# Modulator.net
KiCad netlist of a schematic drawn in Altium Designer
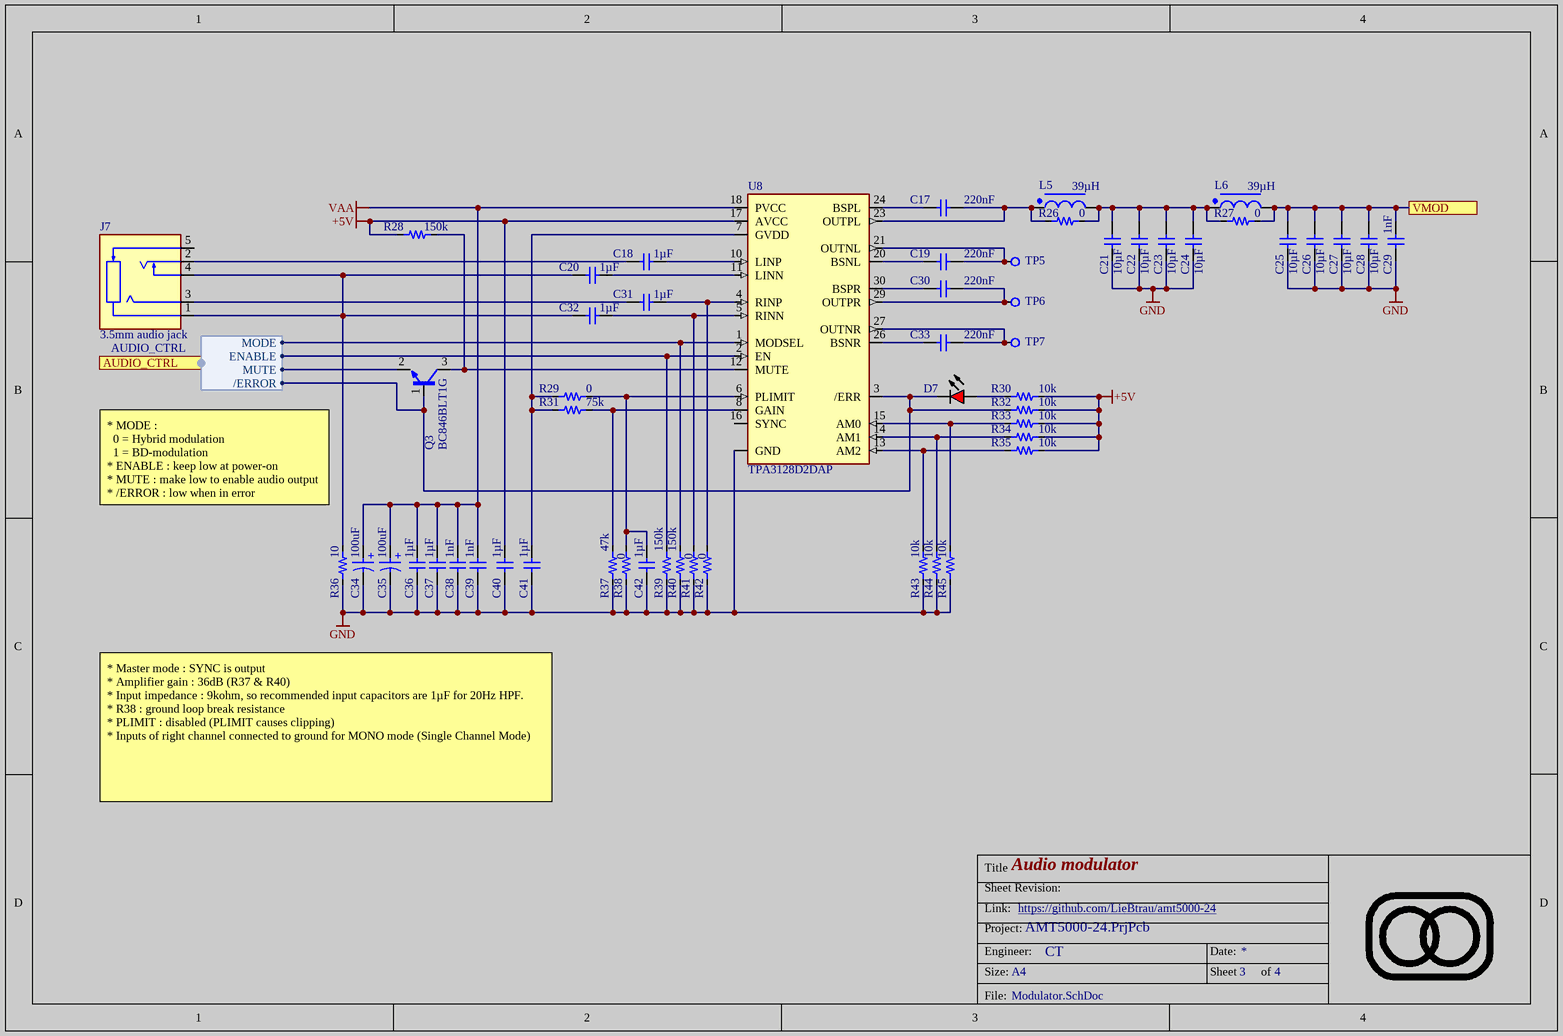
[diagram p0: Modulator.SchDoc]

(export (version "E")
  (design (tool "Eeschema 10.0.6"))
  (components
    (comp (ref "C17")
      (value "220nF")
      (footprint "0805-C-N")
      (description "WCAP-CSGP Multilayer Ceramic Chip Capacitor, General Purpose, size 0805, X7R, 220nF, 50VDC")
      (fields (field (name "JLCPCB PART #") "C5378") (field (name "TOLERANCE") "10%"))
      (libsource (lib "7c7 Engineering") (part "CAP-NP-2"))
    )
    (comp (ref "C18")
      (value "1µF")
      (footprint "1206-C-N")
      (description "WCAP-CSGP Multilayer Ceramic Chip Capacitor, General Purpose, size 1206, X7R, 1µF, 50VDC")
      (fields (field (name "TOLERANCE") "10%") (field (name "JLCPCB PART #") "C1848"))
      (libsource (lib "7c7 Engineering") (part "CAP-NP-2"))
    )
    (comp (ref "C19")
      (value "220nF")
      (footprint "0805-C-N")
      (description "WCAP-CSGP Multilayer Ceramic Chip Capacitor, General Purpose, size 0805, X7R, 220nF, 50VDC")
      (fields (field (name "JLCPCB PART #") "C5378") (field (name "TOLERANCE") "10%"))
      (libsource (lib "7c7 Engineering") (part "CAP-NP-2"))
    )
    (comp (ref "C20")
      (value "1µF")
      (footprint "1206-C-N")
      (description "WCAP-CSGP Multilayer Ceramic Chip Capacitor, General Purpose, size 1206, X7R, 1µF, 50VDC")
      (fields (field (name "TOLERANCE") "10%") (field (name "JLCPCB PART #") "C1848"))
      (libsource (lib "7c7 Engineering") (part "CAP-NP-2"))
    )
    (comp (ref "C21")
      (value "10µF")
      (footprint "WCAP-CSGP_1210_L3.2W2.5H2.5")
      (description "WCAP-CSGP Multilayer Ceramic Chip Capacitor, General Purpose, size 1210, X7R, 10µF, 50VDC")
      (fields (field (name "TOLERANCE") "10%") (field (name "JLCPCB PART #") "C2918502"))
      (libsource (lib "7c7 Engineering") (part "CAP-NP-2"))
    )
    (comp (ref "C22")
      (value "10µF")
      (footprint "WCAP-CSGP_1210_L3.2W2.5H2.5")
      (description "WCAP-CSGP Multilayer Ceramic Chip Capacitor, General Purpose, size 1210, X7R, 10µF, 50VDC")
      (fields (field (name "TOLERANCE") "10%") (field (name "JLCPCB PART #") "C2918502"))
      (libsource (lib "7c7 Engineering") (part "CAP-NP-2"))
    )
    (comp (ref "C23")
      (value "10µF")
      (footprint "WCAP-CSGP_1210_L3.2W2.5H2.5")
      (description "WCAP-CSGP Multilayer Ceramic Chip Capacitor, General Purpose, size 1210, X7R, 10µF, 50VDC")
      (fields (field (name "TOLERANCE") "10%") (field (name "JLCPCB PART #") "C2918502"))
      (libsource (lib "7c7 Engineering") (part "CAP-NP-2"))
    )
    (comp (ref "C24")
      (value "10µF")
      (footprint "WCAP-CSGP_1210_L3.2W2.5H2.5")
      (description "WCAP-CSGP Multilayer Ceramic Chip Capacitor, General Purpose, size 1210, X7R, 10µF, 50VDC")
      (fields (field (name "TOLERANCE") "10%") (field (name "JLCPCB PART #") "C2918502"))
      (libsource (lib "7c7 Engineering") (part "CAP-NP-2"))
    )
    (comp (ref "C25")
      (value "10µF")
      (footprint "WCAP-CSGP_1210_L3.2W2.5H2.5")
      (description "WCAP-CSGP Multilayer Ceramic Chip Capacitor, General Purpose, size 1210, X7R, 10µF, 50VDC")
      (fields (field (name "TOLERANCE") "10%") (field (name "JLCPCB PART #") "C2918502"))
      (libsource (lib "7c7 Engineering") (part "CAP-NP-2"))
    )
    (comp (ref "C26")
      (value "10µF")
      (footprint "WCAP-CSGP_1210_L3.2W2.5H2.5")
      (description "WCAP-CSGP Multilayer Ceramic Chip Capacitor, General Purpose, size 1210, X7R, 10µF, 50VDC")
      (fields (field (name "TOLERANCE") "10%") (field (name "JLCPCB PART #") "C2918502"))
      (libsource (lib "7c7 Engineering") (part "CAP-NP-2"))
    )
    (comp (ref "C27")
      (value "10µF")
      (footprint "WCAP-CSGP_1210_L3.2W2.5H2.5")
      (description "WCAP-CSGP Multilayer Ceramic Chip Capacitor, General Purpose, size 1210, X7R, 10µF, 50VDC")
      (fields (field (name "TOLERANCE") "10%") (field (name "JLCPCB PART #") "C2918502"))
      (libsource (lib "7c7 Engineering") (part "CAP-NP-2"))
    )
    (comp (ref "C28")
      (value "10µF")
      (footprint "WCAP-CSGP_1210_L3.2W2.5H2.5")
      (description "WCAP-CSGP Multilayer Ceramic Chip Capacitor, General Purpose, size 1210, X7R, 10µF, 50VDC")
      (fields (field (name "TOLERANCE") "10%") (field (name "JLCPCB PART #") "C2918502"))
      (libsource (lib "7c7 Engineering") (part "CAP-NP-2"))
    )
    (comp (ref "C29")
      (value "1nF")
      (footprint "0603-C-N")
      (description "WCAP-CSGP Multilayer Ceramic Chip Capacitor, General Purpose, size 0603, X7R, 1nF, 100VDC")
      (fields (field (name "JLCPCB PART #") "C182247") (field (name "TOLERANCE") "10%"))
      (libsource (lib "7c7 Engineering") (part "CAP-NP-2"))
    )
    (comp (ref "C30")
      (value "220nF")
      (footprint "0805-C-N")
      (description "WCAP-CSGP Multilayer Ceramic Chip Capacitor, General Purpose, size 0805, X7R, 220nF, 50VDC")
      (fields (field (name "JLCPCB PART #") "C5378") (field (name "TOLERANCE") "10%"))
      (libsource (lib "7c7 Engineering") (part "CAP-NP-2"))
    )
    (comp (ref "C31")
      (value "1µF")
      (footprint "1206-C-N")
      (description "WCAP-CSGP Multilayer Ceramic Chip Capacitor, General Purpose, size 1206, X7R, 1µF, 50VDC")
      (fields (field (name "TOLERANCE") "10%") (field (name "JLCPCB PART #") "C1848"))
      (libsource (lib "7c7 Engineering") (part "CAP-NP-2"))
    )
    (comp (ref "C32")
      (value "1µF")
      (footprint "1206-C-N")
      (description "WCAP-CSGP Multilayer Ceramic Chip Capacitor, General Purpose, size 1206, X7R, 1µF, 50VDC")
      (fields (field (name "TOLERANCE") "10%") (field (name "JLCPCB PART #") "C1848"))
      (libsource (lib "7c7 Engineering") (part "CAP-NP-2"))
    )
    (comp (ref "C33")
      (value "220nF")
      (footprint "0805-C-N")
      (description "WCAP-CSGP Multilayer Ceramic Chip Capacitor, General Purpose, size 0805, X7R, 220nF, 50VDC")
      (fields (field (name "JLCPCB PART #") "C5378") (field (name "TOLERANCE") "10%"))
      (libsource (lib "7c7 Engineering") (part "CAP-NP-2"))
    )
    (comp (ref "C34")
      (value "875585545003")
      (footprint "WCAP-HSAH_D6.3H7.7")
      (description "WCAP-HSAH Aluminum Hybrid Polymer Capacitor, SMT, D6.3 x H7.7mm, 100uF, 25V")
      (fields
        (field (name "JLCPCB PART #") "C22395169")
        (field (name "CAPACITANCE") "100uF")
        (field (name "MANUFACTURER") "Wurth Elektronik")
      )
      (libsource (lib "7c7 Engineering") (part "875585961005"))
    )
    (comp (ref "C35")
      (value "875585545003")
      (footprint "WCAP-HSAH_D6.3H7.7")
      (description "WCAP-HSAH Aluminum Hybrid Polymer Capacitor, SMT, D6.3 x H7.7mm, 100uF, 25V")
      (fields
        (field (name "JLCPCB PART #") "C22395169")
        (field (name "CAPACITANCE") "100uF")
        (field (name "MANUFACTURER") "Wurth Elektronik")
      )
      (libsource (lib "7c7 Engineering") (part "875585961005"))
    )
    (comp (ref "C36")
      (value "1µF")
      (footprint "1206-C-N")
      (description "WCAP-CSGP Multilayer Ceramic Chip Capacitor, General Purpose, size 1206, X7R, 1µF, 50VDC")
      (fields (field (name "TOLERANCE") "10%") (field (name "JLCPCB PART #") "C1848"))
      (libsource (lib "7c7 Engineering") (part "CAP-NP-2"))
    )
    (comp (ref "C37")
      (value "1µF")
      (footprint "1206-C-N")
      (description "WCAP-CSGP Multilayer Ceramic Chip Capacitor, General Purpose, size 1206, X7R, 1µF, 50VDC")
      (fields (field (name "TOLERANCE") "10%") (field (name "JLCPCB PART #") "C1848"))
      (libsource (lib "7c7 Engineering") (part "CAP-NP-2"))
    )
    (comp (ref "C38")
      (value "1nF")
      (footprint "0603-C-N")
      (description "WCAP-CSGP Multilayer Ceramic Chip Capacitor, General Purpose, size 0603, X7R, 1nF, 100VDC")
      (fields (field (name "JLCPCB PART #") "C182247") (field (name "TOLERANCE") "10%"))
      (libsource (lib "7c7 Engineering") (part "CAP-NP-2"))
    )
    (comp (ref "C39")
      (value "1nF")
      (footprint "0603-C-N")
      (description "WCAP-CSGP Multilayer Ceramic Chip Capacitor, General Purpose, size 0603, X7R, 1nF, 100VDC")
      (fields (field (name "JLCPCB PART #") "C182247") (field (name "TOLERANCE") "10%"))
      (libsource (lib "7c7 Engineering") (part "CAP-NP-2"))
    )
    (comp (ref "C40")
      (value "1µF")
      (footprint "1206-C-N")
      (description "WCAP-CSGP Multilayer Ceramic Chip Capacitor, General Purpose, size 1206, X7R, 1µF, 50VDC")
      (fields (field (name "TOLERANCE") "10%") (field (name "JLCPCB PART #") "C1848"))
      (libsource (lib "7c7 Engineering") (part "CAP-NP-2"))
    )
    (comp (ref "C41")
      (value "1µF")
      (footprint "1206-C-N")
      (description "WCAP-CSGP Multilayer Ceramic Chip Capacitor, General Purpose, size 1206, X7R, 1µF, 50VDC")
      (fields (field (name "TOLERANCE") "10%") (field (name "JLCPCB PART #") "C1848"))
      (libsource (lib "7c7 Engineering") (part "CAP-NP-2"))
    )
    (comp (ref "C42")
      (value "1µF")
      (footprint "1206-C-N")
      (description "WCAP-CSGP Multilayer Ceramic Chip Capacitor, General Purpose, size 1206, X7R, 1µF, 50VDC")
      (fields (field (name "TOLERANCE") "10%") (field (name "JLCPCB PART #") "C1848"))
      (libsource (lib "7c7 Engineering") (part "CAP-NP-2"))
    )
    (comp (ref "D7")
      (value "150060RS86000")
      (footprint "WL-SMCW_0603_150060xx8x000")
      (description "WL-SMCW Mono-color Chip LED Waterclear, size 0603, Red, 2V, 60°")
      (fields (field (name "JLCPCB PART #") "C5875741") (field (name "MANUFACTURER") "Wurth Elektronik"))
      (libsource (lib "7c7 Engineering") (part "LED-RED-2"))
    )
    (comp (ref "J7")
      (value "3.5mm audio jack")
      (footprint "SJ2-35863B1-SMT-TR-Footprint-1")
      (description "3.5 mm, Stereo, Right Angle, Surface Mount (SMT), Audio Jack Connector")
      (fields (field (name "JLCPCB PART #") "C381135"))
      (libsource (lib "7c7 Engineering") (part "CN_AUDIO_TRS_2SW"))
    )
    (comp (ref "L5")
      (value "744776139")
      (footprint "WE-PD2_1054")
      (description "WE-PD2 SMT Power Inductor, size 1054, 39µH, 1.62A, 0.14O")
      (fields (field (name "INDUCTANCE") "39µH") (field (name "MANUFACTURER") "Wurth Elektronik"))
      (libsource (lib "7c7 Engineering") (part "IND-CORE-2"))
    )
    (comp (ref "L6")
      (value "744776139")
      (footprint "WE-PD2_1054")
      (description "WE-PD2 SMT Power Inductor, size 1054, 39µH, 1.62A, 0.14O")
      (fields (field (name "INDUCTANCE") "39µH") (field (name "MANUFACTURER") "Wurth Elektronik"))
      (libsource (lib "7c7 Engineering") (part "IND-CORE-2"))
    )
    (comp (ref "Q3")
      (value "BC846BLT1G")
      (footprint "SOT-23-3-N")
      (description "NPN Ic=100mA Vceo=65V hfe=200~450 P=225mW SOT-23")
      (fields (field (name "JLCPCB PART #") "C82477"))
      (libsource (lib "7c7 Engineering") (part "BJT-NPN-BEC"))
    )
    (comp (ref "R26")
      (value "0")
      (footprint "1206-R-N")
      (description "Chip Jumper, Thick Film, Jumper, 1206, 250mW, 2A, 0 Ohm, <50 mOhm")
      (fields (field (name "JLCPCB PART #") "C17888") (field (name "TOLERANCE") "50 mOhm"))
      (libsource (lib "7c7 Engineering") (part "RES"))
    )
    (comp (ref "R27")
      (value "0")
      (footprint "1206-R-N")
      (description "Chip Jumper, Thick Film, Jumper, 1206, 250mW, 2A, 0 Ohm, <50 mOhm")
      (fields (field (name "JLCPCB PART #") "C17888") (field (name "TOLERANCE") "50 mOhm"))
      (libsource (lib "7c7 Engineering") (part "RES"))
    )
    (comp (ref "R28")
      (value "150k")
      (footprint "0603-R-N")
      (description "Chip Resistor, Thick Film, General Purpose, 0603, 100mW, 50V, 150 kOhm, +/-1%")
      (fields (field (name "FLIR PART #") "YRES150K-1") (field (name "JLCPCB PART #") "C22807"))
      (libsource (lib "7c7 Engineering") (part "RES"))
    )
    (comp (ref "R29")
      (value "0")
      (footprint "0603-R-N")
      (description "Chip Jumper, Thick Film, Jumper, 0603, 100mW, 1A, 0 Ohm, <50 mOhm")
      (fields (field (name "FLIR PART #") "YRES0E-1") (field (name "TOLERANCE") "50 mOhm"))
      (libsource (lib "7c7 Engineering") (part "RES"))
    )
    (comp (ref "R30")
      (value "10k")
      (footprint "0603-R-N")
      (description "Chip Resistor, Thick Film, General Purpose, 0603, 100mW, 50V, 10 kOhm, +/-1%")
      (fields (field (name "JLCPCB PART #") "C25804") (field (name "FLIR PART #") "YRES10K-1"))
      (libsource (lib "7c7 Engineering") (part "RES"))
    )
    (comp (ref "R31")
      (value "75k")
      (footprint "0603-R-N")
      (description "Chip Resistor, Thick Film, General Purpose, 0603, 100mW, 50V, 75 kOhm, +/-1%")
      (fields (field (name "JLCPCB PART #") "C23242") (field (name "TOLERANCE") "1%"))
      (libsource (lib "7c7 Engineering") (part "RES"))
    )
    (comp (ref "R32")
      (value "10k")
      (footprint "0603-R-N")
      (description "Chip Resistor, Thick Film, General Purpose, 0603, 100mW, 50V, 10 kOhm, +/-1%")
      (fields (field (name "JLCPCB PART #") "C25804") (field (name "FLIR PART #") "YRES10K-1"))
      (libsource (lib "7c7 Engineering") (part "RES"))
    )
    (comp (ref "R33")
      (value "10k")
      (footprint "0603-R-N")
      (description "Chip Resistor, Thick Film, General Purpose, 0603, 100mW, 50V, 10 kOhm, +/-1%")
      (fields (field (name "JLCPCB PART #") "C25804") (field (name "FLIR PART #") "YRES10K-1"))
      (libsource (lib "7c7 Engineering") (part "RES"))
    )
    (comp (ref "R34")
      (value "10k")
      (footprint "0603-R-N")
      (description "Chip Resistor, Thick Film, General Purpose, 0603, 100mW, 50V, 10 kOhm, +/-1%")
      (fields (field (name "JLCPCB PART #") "C25804") (field (name "FLIR PART #") "YRES10K-1"))
      (libsource (lib "7c7 Engineering") (part "RES"))
    )
    (comp (ref "R35")
      (value "10k")
      (footprint "0603-R-N")
      (description "Chip Resistor, Thick Film, General Purpose, 0603, 100mW, 50V, 10 kOhm, +/-1%")
      (fields (field (name "JLCPCB PART #") "C25804") (field (name "FLIR PART #") "YRES10K-1"))
      (libsource (lib "7c7 Engineering") (part "RES"))
    )
    (comp (ref "R36")
      (value "10")
      (footprint "0603-R-N")
      (description "Chip Resistor, Thick Film, General Purpose, 0603, 100mW, 50V, 10 Ohm, +/-1%")
      (fields (field (name "TOLERANCE") "1%") (field (name "JLCPCB PART #") "C22859"))
      (libsource (lib "7c7 Engineering") (part "RES"))
    )
    (comp (ref "R37")
      (value "47k")
      (footprint "0603-R-N")
      (description "Chip Resistor, Thick Film, General Purpose, 0603, 100mW, 50V, 47 kOhm, +/-1%")
      (fields (field (name "JLCPCB PART #") "C25819") (field (name "TOLERANCE") "1%"))
      (libsource (lib "7c7 Engineering") (part "RES"))
    )
    (comp (ref "R38")
      (value "0")
      (footprint "0603-R-N")
      (description "Chip Jumper, Thick Film, Jumper, 0603, 100mW, 1A, 0 Ohm, <50 mOhm")
      (fields (field (name "FLIR PART #") "YRES0E-1") (field (name "TOLERANCE") "50 mOhm"))
      (libsource (lib "7c7 Engineering") (part "RES"))
    )
    (comp (ref "R39")
      (value "150k")
      (footprint "0603-R-N")
      (description "Chip Resistor, Thick Film, General Purpose, 0603, 100mW, 50V, 150 kOhm, +/-1%")
      (fields (field (name "FLIR PART #") "YRES150K-1") (field (name "JLCPCB PART #") "C22807"))
      (libsource (lib "7c7 Engineering") (part "RES"))
    )
    (comp (ref "R40")
      (value "150k")
      (footprint "0603-R-N")
      (description "Chip Resistor, Thick Film, General Purpose, 0603, 100mW, 50V, 150 kOhm, +/-1%")
      (fields (field (name "FLIR PART #") "YRES150K-1") (field (name "JLCPCB PART #") "C22807"))
      (libsource (lib "7c7 Engineering") (part "RES"))
    )
    (comp (ref "R41")
      (value "0")
      (footprint "0603-R-N")
      (description "Chip Jumper, Thick Film, Jumper, 0603, 100mW, 1A, 0 Ohm, <50 mOhm")
      (fields (field (name "FLIR PART #") "YRES0E-1") (field (name "TOLERANCE") "50 mOhm"))
      (libsource (lib "7c7 Engineering") (part "RES"))
    )
    (comp (ref "R42")
      (value "0")
      (footprint "0603-R-N")
      (description "Chip Jumper, Thick Film, Jumper, 0603, 100mW, 1A, 0 Ohm, <50 mOhm")
      (fields (field (name "FLIR PART #") "YRES0E-1") (field (name "TOLERANCE") "50 mOhm"))
      (libsource (lib "7c7 Engineering") (part "RES"))
    )
    (comp (ref "R43")
      (value "10k")
      (footprint "0603-R-N")
      (description "Chip Resistor, Thick Film, General Purpose, 0603, 100mW, 50V, 10 kOhm, +/-1%")
      (fields (field (name "JLCPCB PART #") "C25804") (field (name "FLIR PART #") "YRES10K-1"))
      (libsource (lib "7c7 Engineering") (part "RES"))
    )
    (comp (ref "R44")
      (value "10k")
      (footprint "0603-R-N")
      (description "Chip Resistor, Thick Film, General Purpose, 0603, 100mW, 50V, 10 kOhm, +/-1%")
      (fields (field (name "JLCPCB PART #") "C25804") (field (name "FLIR PART #") "YRES10K-1"))
      (libsource (lib "7c7 Engineering") (part "RES"))
    )
    (comp (ref "R45")
      (value "10k")
      (footprint "0603-R-N")
      (description "Chip Resistor, Thick Film, General Purpose, 0603, 100mW, 50V, 10 kOhm, +/-1%")
      (fields (field (name "JLCPCB PART #") "C25804") (field (name "FLIR PART #") "YRES10K-1"))
      (libsource (lib "7c7 Engineering") (part "RES"))
    )
    (comp (ref "TP5")
      (value "Testpad with multiple sizes")
      (footprint "TP_1.5mm")
      (description "Testpad land")
      (libsource (lib "7c7 Engineering") (part "Testpad"))
    )
    (comp (ref "TP6")
      (value "Testpad with multiple sizes")
      (footprint "TP_1.5mm")
      (description "Testpad land")
      (libsource (lib "7c7 Engineering") (part "Testpad"))
    )
    (comp (ref "TP7")
      (value "Testpad with multiple sizes")
      (footprint "TP_1.5mm")
      (description "Testpad land")
      (libsource (lib "7c7 Engineering") (part "Testpad"))
    )
    (comp (ref "U8")
      (value "TPA3128D2DAP")
      (footprint "TSSOP28_PPad")
      (description "Audio Amp Speaker 1-CH Mono/2-CH Stereo 60W Class-D 32-Pin HTSSOP EP Tube")
      (fields (field (name "JLCPCB PART #") "C473362"))
      (libsource (lib "7c7 Engineering") (part "IC_TPA31xx"))
    )
  )
  (nets
    (net (code "2") (name "+5V") (class "Default")
      (node (ref "C40") (pin "2") (pinfunction "2_2") (pintype "passive"))
      (node (ref "R28") (pin "1") (pinfunction "1_1") (pintype "passive"))
      (node (ref "R30") (pin "2") (pinfunction "2_2") (pintype "passive"))
      (node (ref "R32") (pin "1") (pinfunction "1_1") (pintype "passive"))
      (node (ref "R33") (pin "1") (pinfunction "1_1") (pintype "passive"))
      (node (ref "R34") (pin "1") (pinfunction "1_1") (pintype "passive"))
      (node (ref "R35") (pin "1") (pinfunction "1_1") (pintype "passive"))
      (node (ref "U8") (pin "17") (pinfunction "AVCC_17") (pintype "power_in"))
    )
    (net (code "3") (name "/VMOD") (class "Default")
      (node (ref "C25") (pin "2") (pinfunction "2_2") (pintype "passive"))
      (node (ref "C26") (pin "2") (pinfunction "2_2") (pintype "passive"))
      (node (ref "C27") (pin "2") (pinfunction "2_2") (pintype "passive"))
      (node (ref "C28") (pin "2") (pinfunction "2_2") (pintype "passive"))
      (node (ref "C29") (pin "2") (pinfunction "2_2") (pintype "passive"))
      (node (ref "L6") (pin "2") (pinfunction "2_2") (pintype "passive"))
      (node (ref "R27") (pin "2") (pinfunction "2_2") (pintype "passive"))
    )
    (net (code "5") (name "GND") (class "Default")
      (node (ref "C21") (pin "1") (pinfunction "1_1") (pintype "passive"))
      (node (ref "C22") (pin "1") (pinfunction "1_1") (pintype "passive"))
      (node (ref "C23") (pin "1") (pinfunction "1_1") (pintype "passive"))
      (node (ref "C24") (pin "1") (pinfunction "1_1") (pintype "passive"))
      (node (ref "C25") (pin "1") (pinfunction "1_1") (pintype "passive"))
      (node (ref "C26") (pin "1") (pinfunction "1_1") (pintype "passive"))
      (node (ref "C27") (pin "1") (pinfunction "1_1") (pintype "passive"))
      (node (ref "C28") (pin "1") (pinfunction "1_1") (pintype "passive"))
      (node (ref "C29") (pin "1") (pinfunction "1_1") (pintype "passive"))
      (node (ref "C34") (pin "2") (pinfunction "N_2") (pintype "passive"))
      (node (ref "C35") (pin "2") (pinfunction "N_2") (pintype "passive"))
      (node (ref "C36") (pin "2") (pinfunction "2_2") (pintype "passive"))
      (node (ref "C37") (pin "2") (pinfunction "2_2") (pintype "passive"))
      (node (ref "C38") (pin "1") (pinfunction "1_1") (pintype "passive"))
      (node (ref "C39") (pin "1") (pinfunction "1_1") (pintype "passive"))
      (node (ref "C40") (pin "1") (pinfunction "1_1") (pintype "passive"))
      (node (ref "C41") (pin "1") (pinfunction "1_1") (pintype "passive"))
      (node (ref "C42") (pin "1") (pinfunction "1_1") (pintype "passive"))
      (node (ref "R36") (pin "1") (pinfunction "1_1") (pintype "passive"))
      (node (ref "R37") (pin "1") (pinfunction "1_1") (pintype "passive"))
      (node (ref "R38") (pin "1") (pinfunction "1_1") (pintype "passive"))
      (node (ref "R39") (pin "1") (pinfunction "1_1") (pintype "passive"))
      (node (ref "R40") (pin "1") (pinfunction "1_1") (pintype "passive"))
      (node (ref "R41") (pin "1") (pinfunction "1_1") (pintype "passive"))
      (node (ref "R42") (pin "1") (pinfunction "1_1") (pintype "passive"))
      (node (ref "R43") (pin "2") (pinfunction "2_2") (pintype "passive"))
      (node (ref "R44") (pin "2") (pinfunction "2_2") (pintype "passive"))
      (node (ref "R45") (pin "2") (pinfunction "2_2") (pintype "passive"))
      (node (ref "U8") (pin "9") (pinfunction "GND_9") (pintype "passive"))
    )
    (net (code "6") (name "Net-(C18-Pad2)") (class "Default")
      (node (ref "C18") (pin "2") (pinfunction "2_2") (pintype "passive"))
      (node (ref "J7") (pin "2") (pinfunction "2_2") (pintype "passive"))
    )
    (net (code "7") (name "Net-(C20-Pad2)") (class "Default")
      (node (ref "C20") (pin "2") (pinfunction "2_2") (pintype "passive"))
      (node (ref "C32") (pin "2") (pinfunction "2_2") (pintype "passive"))
      (node (ref "J7") (pin "1") (pinfunction "1_1") (pintype "passive"))
      (node (ref "J7") (pin "4") (pinfunction "4_4") (pintype "passive"))
      (node (ref "R36") (pin "2") (pinfunction "2_2") (pintype "passive"))
    )
    (net (code "8") (name "Net-(C21-Pad2)") (class "Default")
      (node (ref "C21") (pin "2") (pinfunction "2_2") (pintype "passive"))
      (node (ref "C22") (pin "2") (pinfunction "2_2") (pintype "passive"))
      (node (ref "C23") (pin "2") (pinfunction "2_2") (pintype "passive"))
      (node (ref "C24") (pin "2") (pinfunction "2_2") (pintype "passive"))
      (node (ref "L5") (pin "2") (pinfunction "2_2") (pintype "passive"))
      (node (ref "L6") (pin "1") (pinfunction "1_1") (pintype "passive"))
      (node (ref "R26") (pin "2") (pinfunction "2_2") (pintype "passive"))
      (node (ref "R27") (pin "1") (pinfunction "1_1") (pintype "passive"))
    )
    (net (code "9") (name "Net-(C31-Pad2)") (class "Default")
      (node (ref "C31") (pin "2") (pinfunction "2_2") (pintype "passive"))
      (node (ref "J7") (pin "3") (pinfunction "3_3") (pintype "passive"))
    )
    (net (code "10") (name "Net-(D7-A)") (class "Default")
      (node (ref "D7") (pin "2") (pinfunction "A_2") (pintype "passive"))
      (node (ref "R30") (pin "1") (pinfunction "1_1") (pintype "passive"))
    )
    (net (code "11") (name "Net-(D7-K)") (class "Default")
      (node (ref "D7") (pin "1") (pinfunction "K_1") (pintype "passive"))
      (node (ref "Q3") (pin "1") (pinfunction "B_1") (pintype "passive"))
      (node (ref "R32") (pin "2") (pinfunction "2_2") (pintype "passive"))
      (node (ref "U8") (pin "3") (pinfunction "/ERR_3") (pintype "open_collector"))
    )
    (net (code "12") (name "Net-(Q3-C)") (class "Default")
      (node (ref "Q3") (pin "3") (pinfunction "C_3") (pintype "passive"))
      (node (ref "R28") (pin "2") (pinfunction "2_2") (pintype "passive"))
      (node (ref "U8") (pin "12") (pinfunction "MUTE_12") (pintype "passive"))
    )
    (net (code "13") (name "Net-(U8-AM0)") (class "Default")
      (node (ref "R33") (pin "2") (pinfunction "2_2") (pintype "passive"))
      (node (ref "R45") (pin "1") (pinfunction "1_1") (pintype "passive"))
      (node (ref "U8") (pin "15") (pinfunction "AM0_15") (pintype "input"))
    )
    (net (code "14") (name "Net-(U8-AM1)") (class "Default")
      (node (ref "R34") (pin "2") (pinfunction "2_2") (pintype "passive"))
      (node (ref "R44") (pin "1") (pinfunction "1_1") (pintype "passive"))
      (node (ref "U8") (pin "14") (pinfunction "AM1_14") (pintype "input"))
    )
    (net (code "15") (name "Net-(U8-AM2)") (class "Default")
      (node (ref "R35") (pin "2") (pinfunction "2_2") (pintype "passive"))
      (node (ref "R43") (pin "1") (pinfunction "1_1") (pintype "passive"))
      (node (ref "U8") (pin "13") (pinfunction "AM2_13") (pintype "input"))
    )
    (net (code "16") (name "Net-(U8-BSNL)") (class "Default")
      (node (ref "C19") (pin "1") (pinfunction "1_1") (pintype "passive"))
      (node (ref "U8") (pin "20") (pinfunction "BSNL_20") (pintype "passive"))
    )
    (net (code "17") (name "Net-(U8-BSNR)") (class "Default")
      (node (ref "C33") (pin "1") (pinfunction "1_1") (pintype "passive"))
      (node (ref "U8") (pin "26") (pinfunction "BSNR_26") (pintype "passive"))
    )
    (net (code "18") (name "Net-(U8-BSPL)") (class "Default")
      (node (ref "C17") (pin "1") (pinfunction "1_1") (pintype "passive"))
      (node (ref "U8") (pin "24") (pinfunction "BSPL_24") (pintype "passive"))
    )
    (net (code "19") (name "Net-(U8-BSPR)") (class "Default")
      (node (ref "C30") (pin "1") (pinfunction "1_1") (pintype "passive"))
      (node (ref "U8") (pin "30") (pinfunction "BSPR_30") (pintype "passive"))
    )
    (net (code "20") (name "Net-(U8-EN)") (class "Default")
      (node (ref "R39") (pin "2") (pinfunction "2_2") (pintype "passive"))
      (node (ref "U8") (pin "2") (pinfunction "EN_2") (pintype "input"))
    )
    (net (code "21") (name "Net-(U8-GAIN)") (class "Default")
      (node (ref "R31") (pin "1") (pinfunction "1_1") (pintype "passive"))
      (node (ref "R37") (pin "2") (pinfunction "2_2") (pintype "passive"))
      (node (ref "U8") (pin "8") (pinfunction "GAIN_8") (pintype "passive"))
    )
    (net (code "22") (name "Net-(U8-GVDD)") (class "Default")
      (node (ref "C41") (pin "2") (pinfunction "2_2") (pintype "passive"))
      (node (ref "R29") (pin "1") (pinfunction "1_1") (pintype "passive"))
      (node (ref "R31") (pin "2") (pinfunction "2_2") (pintype "passive"))
      (node (ref "U8") (pin "7") (pinfunction "GVDD_7") (pintype "power_in"))
    )
    (net (code "23") (name "Net-(U8-LINN)") (class "Default")
      (node (ref "C20") (pin "1") (pinfunction "1_1") (pintype "passive"))
      (node (ref "U8") (pin "11") (pinfunction "LINN_11") (pintype "input"))
    )
    (net (code "24") (name "Net-(U8-LINP)") (class "Default")
      (node (ref "C18") (pin "1") (pinfunction "1_1") (pintype "passive"))
      (node (ref "U8") (pin "10") (pinfunction "LINP_10") (pintype "input"))
    )
    (net (code "25") (name "Net-(U8-MODSEL)") (class "Default")
      (node (ref "R40") (pin "2") (pinfunction "2_2") (pintype "passive"))
      (node (ref "U8") (pin "1") (pinfunction "MODSEL_1") (pintype "input"))
    )
    (net (code "26") (name "Net-(U8-OUTNL)") (class "Default")
      (node (ref "C19") (pin "2") (pinfunction "2_2") (pintype "passive"))
      (node (ref "TP5") (pin "1") (pinfunction "Pad_1") (pintype "passive"))
      (node (ref "U8") (pin "21") (pinfunction "OUTNL_21") (pintype "output"))
    )
    (net (code "27") (name "Net-(U8-OUTNR)") (class "Default")
      (node (ref "C33") (pin "2") (pinfunction "2_2") (pintype "passive"))
      (node (ref "TP7") (pin "1") (pinfunction "Pad_1") (pintype "passive"))
      (node (ref "U8") (pin "27") (pinfunction "OUTNR_27") (pintype "output"))
    )
    (net (code "28") (name "Net-(U8-OUTPL)") (class "Default")
      (node (ref "C17") (pin "2") (pinfunction "2_2") (pintype "passive"))
      (node (ref "L5") (pin "1") (pinfunction "1_1") (pintype "passive"))
      (node (ref "R26") (pin "1") (pinfunction "1_1") (pintype "passive"))
      (node (ref "U8") (pin "23") (pinfunction "OUTPL_23") (pintype "output"))
    )
    (net (code "29") (name "Net-(U8-OUTPR)") (class "Default")
      (node (ref "C30") (pin "2") (pinfunction "2_2") (pintype "passive"))
      (node (ref "TP6") (pin "1") (pinfunction "Pad_1") (pintype "passive"))
      (node (ref "U8") (pin "29") (pinfunction "OUTPR_29") (pintype "output"))
    )
    (net (code "30") (name "Net-(U8-PLIMIT)") (class "Default")
      (node (ref "C42") (pin "2") (pinfunction "2_2") (pintype "passive"))
      (node (ref "R29") (pin "2") (pinfunction "2_2") (pintype "passive"))
      (node (ref "R38") (pin "2") (pinfunction "2_2") (pintype "passive"))
      (node (ref "U8") (pin "6") (pinfunction "PLIMIT_6") (pintype "input"))
    )
    (net (code "31") (name "Net-(U8-RINN)") (class "Default")
      (node (ref "C32") (pin "1") (pinfunction "1_1") (pintype "passive"))
      (node (ref "R41") (pin "2") (pinfunction "2_2") (pintype "passive"))
      (node (ref "U8") (pin "5") (pinfunction "RINN_5") (pintype "input"))
    )
    (net (code "32") (name "Net-(U8-RINP)") (class "Default")
      (node (ref "C31") (pin "1") (pinfunction "1_1") (pintype "passive"))
      (node (ref "R42") (pin "2") (pinfunction "2_2") (pintype "passive"))
      (node (ref "U8") (pin "4") (pinfunction "RINP_4") (pintype "input"))
    )
    (net (code "33") (name "VAA") (class "Default")
      (node (ref "C34") (pin "1") (pinfunction "P_1") (pintype "passive"))
      (node (ref "C35") (pin "1") (pinfunction "P_1") (pintype "passive"))
      (node (ref "C36") (pin "1") (pinfunction "1_1") (pintype "passive"))
      (node (ref "C37") (pin "1") (pinfunction "1_1") (pintype "passive"))
      (node (ref "C38") (pin "2") (pinfunction "2_2") (pintype "passive"))
      (node (ref "C39") (pin "2") (pinfunction "2_2") (pintype "passive"))
      (node (ref "U8") (pin "18") (pinfunction "PVCC_18") (pintype "passive"))
    )
    (net (code "34") (name "unconnected-(J7-Pad5)") (class "Default")
      (node (ref "J7") (pin "5") (pinfunction "5_5") (pintype "passive"))
    )
    (net (code "35") (name "unconnected-(Q3-E-Pad2)") (class "Default")
      (node (ref "Q3") (pin "2") (pinfunction "E_2") (pintype "passive"))
    )
    (net (code "36") (name "unconnected-(U8-SYNC-Pad16)") (class "Default")
      (node (ref "U8") (pin "16") (pinfunction "SYNC_16") (pintype "passive"))
    )
  )
)
